# FMC_SDR_top.net
KiCad netlist of a schematic drawn in Altium Designer
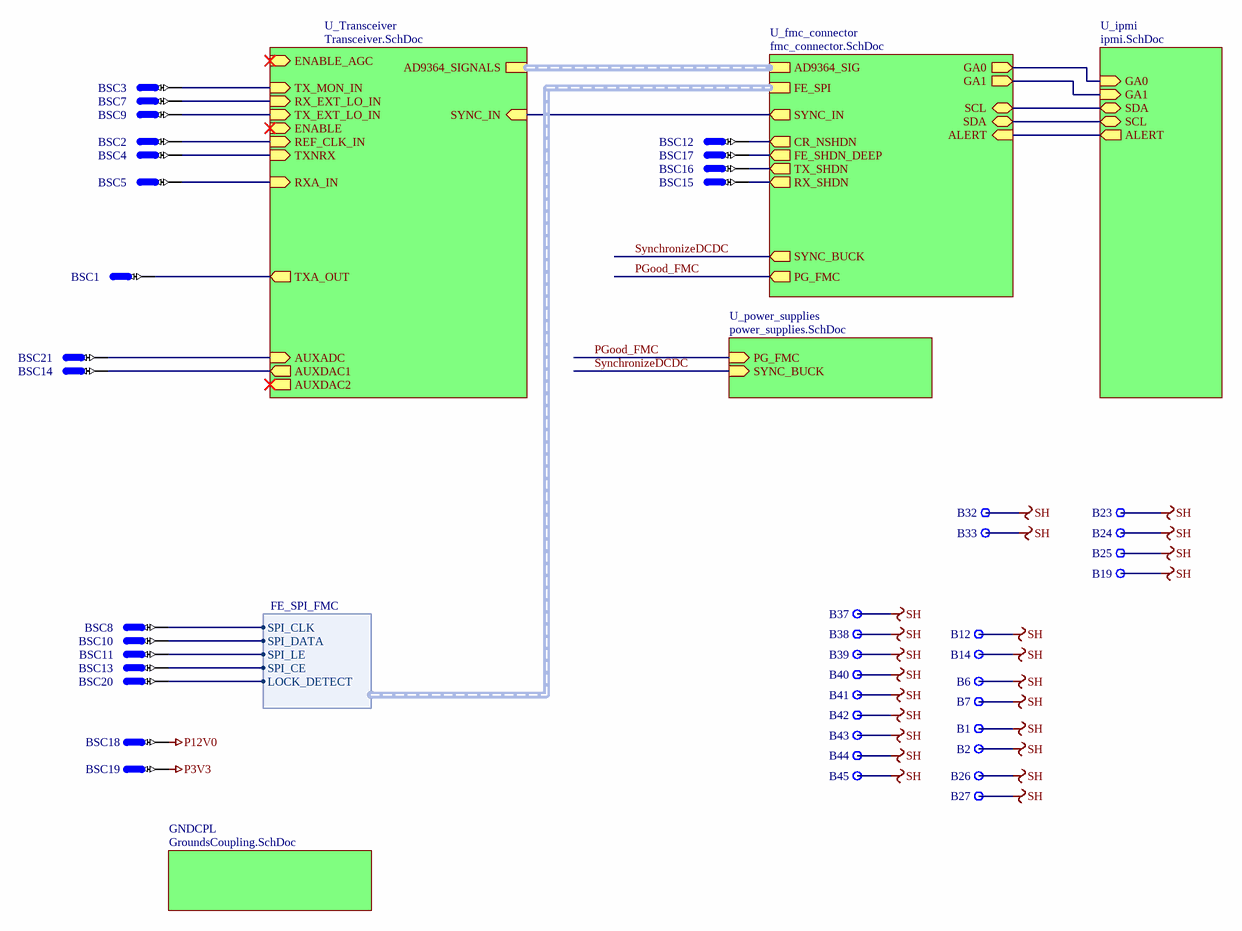
[diagram p0: FMC_SDR_top.SchDoc]

(export (version "E")
  (design (tool "Eeschema 10.0.6"))
  (components
    (comp (ref "B1")
      (value "Plated Hole")
      (footprint "MTG240_400")
      (description "Single Terminal Socket")
      (fields (field (name "PART NUMBER") "PLATED_HOLE2.4_PAD4.0") (field (name "AUTHOR") "CERN DEM JMW"))
      (libsource (lib "Eletro-mechanical") (part "Single Terminal Socket"))
    )
    (comp (ref "B2")
      (value "Plated Hole")
      (footprint "MTG240_400")
      (description "Single Terminal Socket")
      (fields (field (name "PART NUMBER") "PLATED_HOLE2.4_PAD4.0") (field (name "AUTHOR") "CERN DEM JMW"))
      (libsource (lib "Eletro-mechanical") (part "Single Terminal Socket"))
    )
    (comp (ref "B6")
      (value "Plated Hole")
      (footprint "MTG240_400")
      (description "Single Terminal Socket")
      (fields (field (name "PART NUMBER") "PLATED_HOLE2.4_PAD4.0") (field (name "AUTHOR") "CERN DEM JMW"))
      (libsource (lib "Eletro-mechanical") (part "Single Terminal Socket"))
    )
    (comp (ref "B7")
      (value "Plated Hole")
      (footprint "MTG240_400")
      (description "Single Terminal Socket")
      (fields (field (name "PART NUMBER") "PLATED_HOLE2.4_PAD4.0") (field (name "AUTHOR") "CERN DEM JMW"))
      (libsource (lib "Eletro-mechanical") (part "Single Terminal Socket"))
    )
    (comp (ref "B12")
      (value "Plated Hole")
      (footprint "MTG240_400")
      (description "Single Terminal Socket")
      (fields (field (name "PART NUMBER") "PLATED_HOLE2.4_PAD4.0") (field (name "AUTHOR") "CERN DEM JMW"))
      (libsource (lib "Eletro-mechanical") (part "Single Terminal Socket"))
    )
    (comp (ref "B14")
      (value "Plated Hole")
      (footprint "MTG240_400")
      (description "Single Terminal Socket")
      (fields (field (name "PART NUMBER") "PLATED_HOLE2.4_PAD4.0") (field (name "AUTHOR") "CERN DEM JMW"))
      (libsource (lib "Eletro-mechanical") (part "Single Terminal Socket"))
    )
    (comp (ref "B19")
      (value "Plated Hole")
      (footprint "MTG270_500")
      (description "Single Terminal Socket")
      (fields (field (name "PART NUMBER") "PLATED_HOLE2.7_PAD5.0") (field (name "AUTHOR") "CERN DEM JMW"))
      (libsource (lib "") (part "Single Terminal Socket_1"))
    )
    (comp (ref "B23")
      (value "Plated Hole")
      (footprint "MTG270_500")
      (description "Single Terminal Socket")
      (fields (field (name "PART NUMBER") "PLATED_HOLE2.7_PAD5.0") (field (name "AUTHOR") "CERN DEM JMW"))
      (libsource (lib "") (part "Single Terminal Socket_1"))
    )
    (comp (ref "B24")
      (value "Plated Hole")
      (footprint "MTG270_500")
      (description "Single Terminal Socket")
      (fields (field (name "PART NUMBER") "PLATED_HOLE2.7_PAD5.0") (field (name "AUTHOR") "CERN DEM JMW"))
      (libsource (lib "") (part "Single Terminal Socket_1"))
    )
    (comp (ref "B25")
      (value "Plated Hole")
      (footprint "MTG270_500")
      (description "Single Terminal Socket")
      (fields (field (name "PART NUMBER") "PLATED_HOLE2.7_PAD5.0") (field (name "AUTHOR") "CERN DEM JMW"))
      (libsource (lib "") (part "Single Terminal Socket_1"))
    )
    (comp (ref "B26")
      (value "Plated Hole")
      (footprint "MTG240_400")
      (description "Single Terminal Socket")
      (fields (field (name "PART NUMBER") "PLATED_HOLE2.4_PAD4.0") (field (name "AUTHOR") "CERN DEM JMW"))
      (libsource (lib "Eletro-mechanical") (part "Single Terminal Socket"))
    )
    (comp (ref "B27")
      (value "Plated Hole")
      (footprint "MTG240_400")
      (description "Single Terminal Socket")
      (fields (field (name "PART NUMBER") "PLATED_HOLE2.4_PAD4.0") (field (name "AUTHOR") "CERN DEM JMW"))
      (libsource (lib "Eletro-mechanical") (part "Single Terminal Socket"))
    )
    (comp (ref "B32")
      (value "Plated Hole")
      (footprint "MTG240_400")
      (description "Single Terminal Socket")
      (fields (field (name "PART NUMBER") "PLATED_HOLE2.4_PAD4.0") (field (name "AUTHOR") "CERN DEM JMW"))
      (libsource (lib "Eletro-mechanical") (part "Single Terminal Socket"))
    )
    (comp (ref "B33")
      (value "Plated Hole")
      (footprint "MTG240_400")
      (description "Single Terminal Socket")
      (fields (field (name "PART NUMBER") "PLATED_HOLE2.4_PAD4.0") (field (name "AUTHOR") "CERN DEM JMW"))
      (libsource (lib "Eletro-mechanical") (part "Single Terminal Socket"))
    )
    (comp (ref "B37")
      (value "Plated Hole")
      (footprint "MTG240_400")
      (description "Single Terminal Socket")
      (fields (field (name "PART NUMBER") "PLATED_HOLE2.4_PAD4.0") (field (name "AUTHOR") "CERN DEM JMW"))
      (libsource (lib "Eletro-mechanical") (part "Single Terminal Socket"))
    )
    (comp (ref "B38")
      (value "Plated Hole")
      (footprint "MTG240_400")
      (description "Single Terminal Socket")
      (fields (field (name "PART NUMBER") "PLATED_HOLE2.4_PAD4.0") (field (name "AUTHOR") "CERN DEM JMW"))
      (libsource (lib "Eletro-mechanical") (part "Single Terminal Socket"))
    )
    (comp (ref "B39")
      (value "Plated Hole")
      (footprint "MTG240_400")
      (description "Single Terminal Socket")
      (fields (field (name "PART NUMBER") "PLATED_HOLE2.4_PAD4.0") (field (name "AUTHOR") "CERN DEM JMW"))
      (libsource (lib "Eletro-mechanical") (part "Single Terminal Socket"))
    )
    (comp (ref "B40")
      (value "Plated Hole")
      (footprint "MTG240_400")
      (description "Single Terminal Socket")
      (fields (field (name "PART NUMBER") "PLATED_HOLE2.4_PAD4.0") (field (name "AUTHOR") "CERN DEM JMW"))
      (libsource (lib "Eletro-mechanical") (part "Single Terminal Socket"))
    )
    (comp (ref "B41")
      (value "Plated Hole")
      (footprint "MTG240_400")
      (description "Single Terminal Socket")
      (fields (field (name "PART NUMBER") "PLATED_HOLE2.4_PAD4.0") (field (name "AUTHOR") "CERN DEM JMW"))
      (libsource (lib "Eletro-mechanical") (part "Single Terminal Socket"))
    )
    (comp (ref "B42")
      (value "Plated Hole")
      (footprint "MTG240_400")
      (description "Single Terminal Socket")
      (fields (field (name "PART NUMBER") "PLATED_HOLE2.4_PAD4.0") (field (name "AUTHOR") "CERN DEM JMW"))
      (libsource (lib "Eletro-mechanical") (part "Single Terminal Socket"))
    )
    (comp (ref "B43")
      (value "Plated Hole")
      (footprint "MTG240_400")
      (description "Single Terminal Socket")
      (fields (field (name "PART NUMBER") "PLATED_HOLE2.4_PAD4.0") (field (name "AUTHOR") "CERN DEM JMW"))
      (libsource (lib "Eletro-mechanical") (part "Single Terminal Socket"))
    )
    (comp (ref "B44")
      (value "Plated Hole")
      (footprint "MTG240_400")
      (description "Single Terminal Socket")
      (fields (field (name "PART NUMBER") "PLATED_HOLE2.4_PAD4.0") (field (name "AUTHOR") "CERN DEM JMW"))
      (libsource (lib "Eletro-mechanical") (part "Single Terminal Socket"))
    )
    (comp (ref "B45")
      (value "Plated Hole")
      (footprint "MTG240_400")
      (description "Single Terminal Socket")
      (fields (field (name "PART NUMBER") "PLATED_HOLE2.4_PAD4.0") (field (name "AUTHOR") "CERN DEM JMW"))
      (libsource (lib "Eletro-mechanical") (part "Single Terminal Socket"))
    )
    (comp (ref "BSC1")
      (value "0603 Female")
      (footprint "PCB_CONN_0603F")
      (libsource (lib "FMC_SDR") (part "0603_female_BoardSolderConnector"))
    )
    (comp (ref "BSC2")
      (value "0603 Female")
      (footprint "PCB_CONN_0603F")
      (libsource (lib "FMC_SDR") (part "0603_female_BoardSolderConnector"))
    )
    (comp (ref "BSC3")
      (value "0603 Female")
      (footprint "PCB_CONN_0603F")
      (libsource (lib "FMC_SDR") (part "0603_female_BoardSolderConnector"))
    )
    (comp (ref "BSC4")
      (value "0603 Female")
      (footprint "PCB_CONN_0603F")
      (libsource (lib "FMC_SDR") (part "0603_female_BoardSolderConnector"))
    )
    (comp (ref "BSC5")
      (value "0603 Female")
      (footprint "PCB_CONN_0603F")
      (libsource (lib "FMC_SDR") (part "0603_female_BoardSolderConnector"))
    )
    (comp (ref "BSC7")
      (value "0603 Female")
      (footprint "PCB_CONN_0603F")
      (libsource (lib "FMC_SDR") (part "0603_female_BoardSolderConnector"))
    )
    (comp (ref "BSC8")
      (value "0603 Female")
      (footprint "PCB_CONN_0603F")
      (libsource (lib "FMC_SDR") (part "0603_female_BoardSolderConnector"))
    )
    (comp (ref "BSC9")
      (value "0603 Female")
      (footprint "PCB_CONN_0603F")
      (libsource (lib "FMC_SDR") (part "0603_female_BoardSolderConnector"))
    )
    (comp (ref "BSC10")
      (value "0603 Female")
      (footprint "PCB_CONN_0603F")
      (libsource (lib "FMC_SDR") (part "0603_female_BoardSolderConnector"))
    )
    (comp (ref "BSC11")
      (value "0603 Female")
      (footprint "PCB_CONN_0603F")
      (libsource (lib "FMC_SDR") (part "0603_female_BoardSolderConnector"))
    )
    (comp (ref "BSC12")
      (value "0603 Female")
      (footprint "PCB_CONN_0603F")
      (libsource (lib "FMC_SDR") (part "0603_female_BoardSolderConnector"))
    )
    (comp (ref "BSC13")
      (value "0603 Female")
      (footprint "PCB_CONN_0603F")
      (libsource (lib "FMC_SDR") (part "0603_female_BoardSolderConnector"))
    )
    (comp (ref "BSC14")
      (value "0603 Female")
      (footprint "PCB_CONN_0603F")
      (libsource (lib "FMC_SDR") (part "0603_female_BoardSolderConnector"))
    )
    (comp (ref "BSC15")
      (value "0603 Female")
      (footprint "PCB_CONN_0603F")
      (libsource (lib "FMC_SDR") (part "0603_female_BoardSolderConnector"))
    )
    (comp (ref "BSC16")
      (value "0603 Female")
      (footprint "PCB_CONN_0603F")
      (libsource (lib "FMC_SDR") (part "0603_female_BoardSolderConnector"))
    )
    (comp (ref "BSC17")
      (value "0603 Female")
      (footprint "PCB_CONN_0603F")
      (libsource (lib "FMC_SDR") (part "0603_female_BoardSolderConnector"))
    )
    (comp (ref "BSC18")
      (value "1206 Female")
      (footprint "PCB_CONN_1206F")
      (libsource (lib "FMC_SDR") (part "1206_female_BoardSolderConnector"))
    )
    (comp (ref "BSC19")
      (value "1206 Female")
      (footprint "PCB_CONN_1206F")
      (libsource (lib "FMC_SDR") (part "1206_female_BoardSolderConnector"))
    )
    (comp (ref "BSC20")
      (value "0603 Female")
      (footprint "PCB_CONN_0603F")
      (libsource (lib "FMC_SDR") (part "0603_female_BoardSolderConnector"))
    )
    (comp (ref "BSC21")
      (value "0603 Female")
      (footprint "PCB_CONN_0603F")
      (libsource (lib "FMC_SDR") (part "0603_female_BoardSolderConnector"))
    )
  )
  (nets
    (net (code "4") (name "/AUXADC") (class "Default")
      (node (ref "BSC21") (pin "1") (pinfunction "1_1") (pintype "bidirectional"))
    )
    (net (code "5") (name "/AUXDAC1") (class "Default")
      (node (ref "BSC14") (pin "1") (pinfunction "1_1") (pintype "bidirectional"))
    )
    (net (code "7") (name "/CR_NSHDN") (class "Default")
      (node (ref "BSC12") (pin "1") (pinfunction "1_1") (pintype "bidirectional"))
    )
    (net (code "10") (name "/FE_SHDN_DEEP") (class "Default")
      (node (ref "BSC17") (pin "1") (pinfunction "1_1") (pintype "bidirectional"))
    )
    (net (code "13") (name "/LOCK_DETECT") (class "Default")
      (node (ref "BSC20") (pin "1") (pinfunction "1_1") (pintype "bidirectional"))
    )
    (net (code "15") (name "/REF_CLK_IN") (class "Default")
      (node (ref "BSC2") (pin "1") (pinfunction "1_1") (pintype "bidirectional"))
    )
    (net (code "16") (name "/RXA_IN") (class "Default")
      (node (ref "BSC5") (pin "1") (pinfunction "1_1") (pintype "bidirectional"))
    )
    (net (code "17") (name "/RX_EXT_LO_IN") (class "Default")
      (node (ref "BSC7") (pin "1") (pinfunction "1_1") (pintype "bidirectional"))
    )
    (net (code "18") (name "/RX_SHDN") (class "Default")
      (node (ref "BSC15") (pin "1") (pinfunction "1_1") (pintype "bidirectional"))
    )
    (net (code "21") (name "/SPI_CE") (class "Default")
      (node (ref "BSC13") (pin "1") (pinfunction "1_1") (pintype "bidirectional"))
    )
    (net (code "22") (name "/SPI_CLK") (class "Default")
      (node (ref "BSC8") (pin "1") (pinfunction "1_1") (pintype "bidirectional"))
    )
    (net (code "23") (name "/SPI_DATA") (class "Default")
      (node (ref "BSC10") (pin "1") (pinfunction "1_1") (pintype "bidirectional"))
    )
    (net (code "24") (name "/SPI_LE") (class "Default")
      (node (ref "BSC11") (pin "1") (pinfunction "1_1") (pintype "bidirectional"))
    )
    (net (code "27") (name "/TXA_OUT") (class "Default")
      (node (ref "BSC1") (pin "1") (pinfunction "1_1") (pintype "bidirectional"))
    )
    (net (code "28") (name "/TXNRX") (class "Default")
      (node (ref "BSC4") (pin "1") (pinfunction "1_1") (pintype "bidirectional"))
    )
    (net (code "29") (name "/TX_EXT_LO_IN") (class "Default")
      (node (ref "BSC9") (pin "1") (pinfunction "1_1") (pintype "bidirectional"))
    )
    (net (code "30") (name "/TX_MON_IN") (class "Default")
      (node (ref "BSC3") (pin "1") (pinfunction "1_1") (pintype "bidirectional"))
    )
    (net (code "31") (name "/TX_SHDN") (class "Default")
      (node (ref "BSC16") (pin "1") (pinfunction "1_1") (pintype "bidirectional"))
    )
    (net (code "33") (name "P3V3") (class "Default")
      (node (ref "BSC19") (pin "1") (pinfunction "1_1") (pintype "bidirectional"))
    )
    (net (code "34") (name "P12V0") (class "Default")
      (node (ref "BSC18") (pin "1") (pinfunction "1_1") (pintype "bidirectional"))
    )
    (net (code "35") (name "SH") (class "Default")
      (node (ref "B1") (pin "1") (pinfunction "1_1") (pintype "passive"))
      (node (ref "B12") (pin "1") (pinfunction "1_1") (pintype "passive"))
      (node (ref "B14") (pin "1") (pinfunction "1_1") (pintype "passive"))
      (node (ref "B19") (pin "1") (pinfunction "1_1") (pintype "bidirectional"))
      (node (ref "B2") (pin "1") (pinfunction "1_1") (pintype "passive"))
      (node (ref "B23") (pin "1") (pinfunction "1_1") (pintype "bidirectional"))
      (node (ref "B24") (pin "1") (pinfunction "1_1") (pintype "bidirectional"))
      (node (ref "B25") (pin "1") (pinfunction "1_1") (pintype "bidirectional"))
      (node (ref "B26") (pin "1") (pinfunction "1_1") (pintype "passive"))
      (node (ref "B27") (pin "1") (pinfunction "1_1") (pintype "passive"))
      (node (ref "B32") (pin "1") (pinfunction "1_1") (pintype "passive"))
      (node (ref "B33") (pin "1") (pinfunction "1_1") (pintype "passive"))
      (node (ref "B37") (pin "1") (pinfunction "1_1") (pintype "passive"))
      (node (ref "B38") (pin "1") (pinfunction "1_1") (pintype "passive"))
      (node (ref "B39") (pin "1") (pinfunction "1_1") (pintype "passive"))
      (node (ref "B40") (pin "1") (pinfunction "1_1") (pintype "passive"))
      (node (ref "B41") (pin "1") (pinfunction "1_1") (pintype "passive"))
      (node (ref "B42") (pin "1") (pinfunction "1_1") (pintype "passive"))
      (node (ref "B43") (pin "1") (pinfunction "1_1") (pintype "passive"))
      (node (ref "B44") (pin "1") (pinfunction "1_1") (pintype "passive"))
      (node (ref "B45") (pin "1") (pinfunction "1_1") (pintype "passive"))
      (node (ref "B6") (pin "1") (pinfunction "1_1") (pintype "passive"))
      (node (ref "B7") (pin "1") (pinfunction "1_1") (pintype "passive"))
    )
  )
)
